# Power_USB.net
KiCad netlist of a schematic drawn in Altium Designer
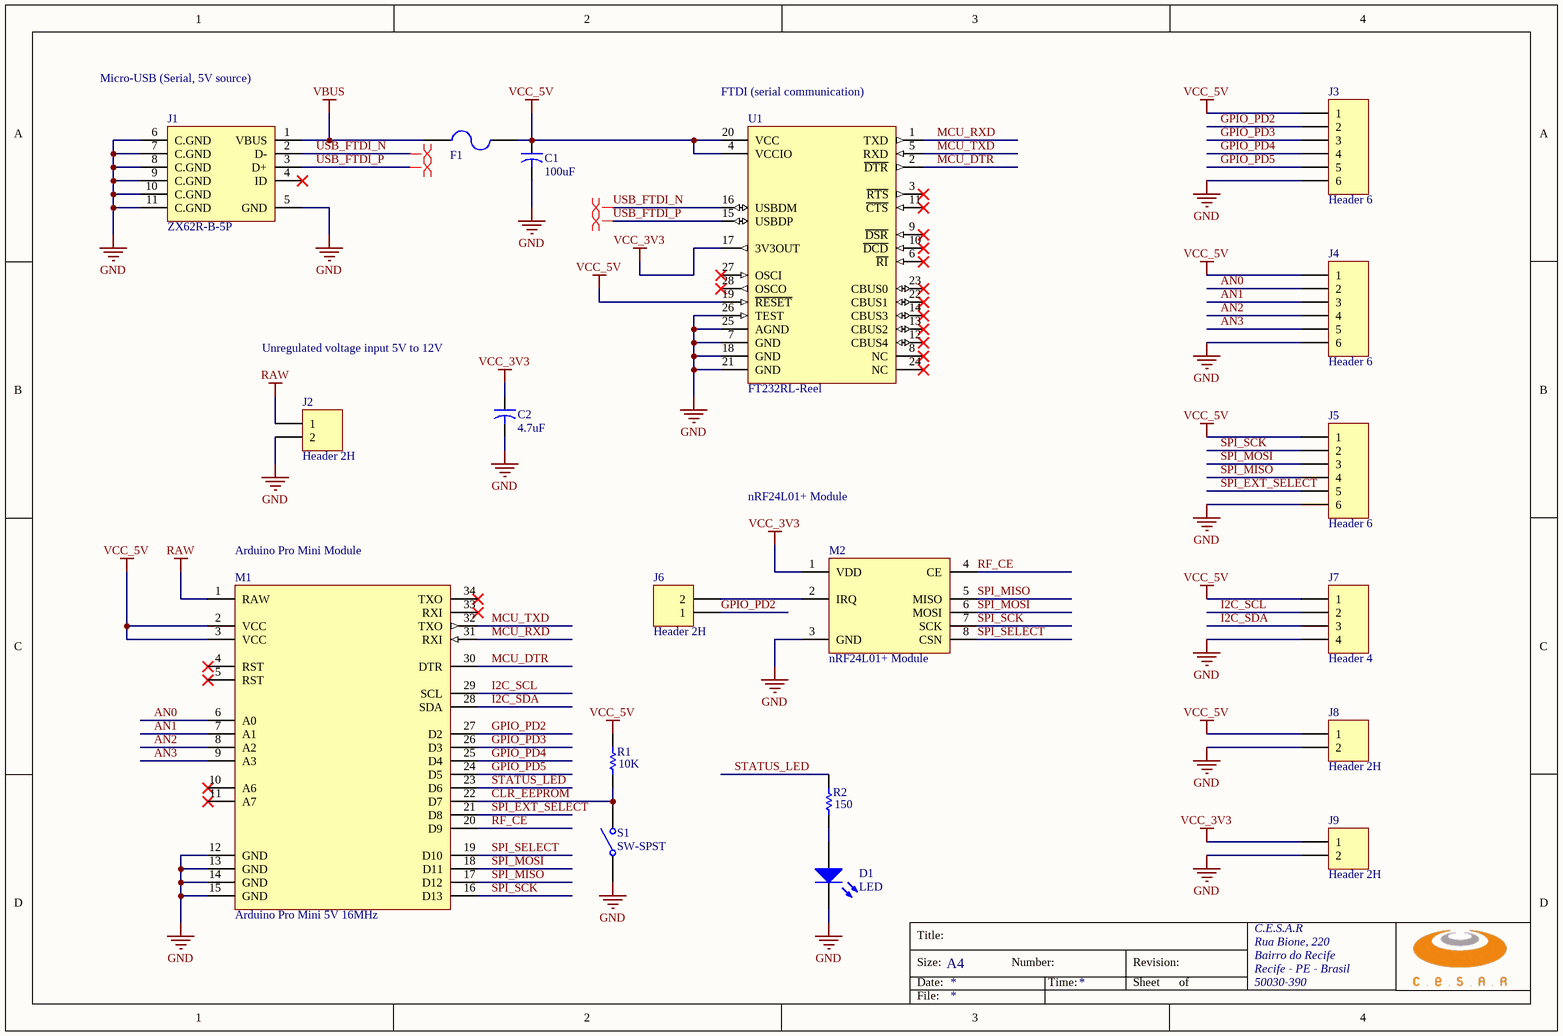
[diagram p0: Power_USB.SchDoc]

(export (version "E")
  (design (tool "Eeschema 10.0.6"))
  (components
    (comp (ref "C1")
      (value "100uF")
      (footprint "CAP Radial 100uF")
      (description "4.7µF 10V Ceramic Capacitor X5R 0603")
      (fields (field (name "Comment") "CAPC1608L") (field (name "PUBLISHER") "Altium Limited"))
      (libsource (lib "KNoT_Thing") (part "CAPC1608L"))
    )
    (comp (ref "C2")
      (value "4.7uF")
      (footprint "CAP RADIAL MINIATURE")
      (description "4.7µF 10V Ceramic Capacitor X5R 0603")
      (fields (field (name "Comment") "CAPC1608L") (field (name "PUBLISHER") "Altium Limited"))
      (libsource (lib "KNoT_Thing") (part "CAPC1608L"))
    )
    (comp (ref "D1")
      (value "LED")
      (footprint "LED")
      (description "Typical RED, GREEN, YELLOW, AMBER GaAs LED")
      (fields (field (name "PUBLISHER") "Altium Limited"))
      (libsource (lib "KNoT_Thing") (part "LED"))
    )
    (comp (ref "F1")
      (value "0402L050SLKR")
      (footprint "0805L")
      (description "PTC Resettable Fuse 6V 500mA Ih Surface Mount 0402 (1005 Metric), Concave")
      (libsource (lib "KNoT_Thing") (part "Fuse 2"))
    )
    (comp (ref "J1")
      (value "ZX62R-B-5P")
      (footprint "Micro USB b")
      (description "USB Connector")
      (libsource (lib "KNoT_Thing") (part "ZX62R-B-5P"))
    )
    (comp (ref "J2")
      (value "Header 2H")
      (footprint "HDR1X2")
      (description "Header, 2-Pin, Right Angle")
      (fields (field (name "PUBLISHER") "Altium Limited"))
      (libsource (lib "KNoT_Thing") (part "Header 2H"))
    )
    (comp (ref "J3")
      (value "Header 6")
      (footprint "HDR1X6")
      (description "Header, 6-Pin")
      (fields (field (name "PUBLISHER") "Altium Limited"))
      (libsource (lib "KNoT_Thing") (part "Header 6"))
    )
    (comp (ref "J4")
      (value "Header 6")
      (footprint "HDR1X6")
      (description "Header, 6-Pin")
      (fields (field (name "PUBLISHER") "Altium Limited"))
      (libsource (lib "KNoT_Thing") (part "Header 6"))
    )
    (comp (ref "J5")
      (value "Header 6")
      (footprint "HDR1X6")
      (description "Header, 6-Pin")
      (fields (field (name "PUBLISHER") "Altium Limited"))
      (libsource (lib "KNoT_Thing") (part "Header 6"))
    )
    (comp (ref "J6")
      (value "Header 2H")
      (footprint "HDR1X2")
      (description "Header, 2-Pin, Right Angle")
      (fields (field (name "PUBLISHER") "Altium Limited"))
      (libsource (lib "") (part "Header 2H_1"))
    )
    (comp (ref "J7")
      (value "Header 4")
      (footprint "HDR1X4")
      (description "Header, 4-Pin")
      (fields (field (name "PUBLISHER") "Altium Limited"))
      (libsource (lib "KNoT_Thing") (part "Header 4"))
    )
    (comp (ref "J8")
      (value "Header 2H")
      (footprint "HDR1X2")
      (description "Header, 2-Pin, Right Angle")
      (fields (field (name "PUBLISHER") "Altium Limited"))
      (libsource (lib "KNoT_Thing") (part "Header 2H"))
    )
    (comp (ref "J9")
      (value "Header 2H")
      (footprint "HDR1X2")
      (description "Header, 2-Pin, Right Angle")
      (fields (field (name "PUBLISHER") "Altium Limited"))
      (libsource (lib "KNoT_Thing") (part "Header 2H"))
    )
    (comp (ref "M1")
      (value "Arduino Pro Mini 5V 16MHz")
      (footprint "Arduino Pro Mini")
      (libsource (lib "KNoT_Thing") (part "Arduino Pro Mini 5V 16MHz"))
    )
    (comp (ref "M2")
      (value "nRF24L01+ Module")
      (footprint "nRF24L01+ Module")
      (libsource (lib "KNoT_Thing") (part "nRF24L01+ Module"))
    )
    (comp (ref "R1")
      (value "10K")
      (footprint "AXIAL-3mm")
      (description "Resistor")
      (fields (field (name "Comment") "Res1") (field (name "PUBLISHER") "Altium Limited"))
      (libsource (lib "KNoT_Thing") (part "Res1"))
    )
    (comp (ref "R2")
      (value "150")
      (footprint "AXIAL-3mm")
      (description "Resistor")
      (fields (field (name "Comment") "Res1") (field (name "PUBLISHER") "Altium Limited"))
      (libsource (lib "KNoT_Thing") (part "Res1"))
    )
    (comp (ref "S1")
      (value "SW-SPST")
      (footprint "SWITCH TS-1181")
      (description "Single-Pole, Single-Throw Switch")
      (fields (field (name "PUBLISHER") "Altium Limited"))
      (libsource (lib "KNoT_Thing") (part "SW-SPST"))
    )
    (comp (ref "U1")
      (value "FT232RL-Reel")
      (footprint "SSOP-28_N")
      (description "USB UART Asynchronous Serial Data Transfer Chip, 28-pin SSOP, Tape and Reel")
      (fields (field (name "MANUFACTURER") "FTDI"))
      (libsource (lib "KNoT_Thing") (part "FT232RL-Reel"))
    )
  )
  (nets
    (net (code "1") (name "/AN0") (class "Default")
      (node (ref "J4") (pin "2") (pinfunction "2_2") (pintype "passive"))
      (node (ref "M1") (pin "6") (pinfunction "A0_6") (pintype "passive"))
    )
    (net (code "2") (name "/AN1") (class "Default")
      (node (ref "J4") (pin "3") (pinfunction "3_3") (pintype "passive"))
      (node (ref "M1") (pin "7") (pinfunction "A1_7") (pintype "passive"))
    )
    (net (code "3") (name "/AN2") (class "Default")
      (node (ref "J4") (pin "4") (pinfunction "4_4") (pintype "passive"))
      (node (ref "M1") (pin "8") (pinfunction "A2_8") (pintype "passive"))
    )
    (net (code "4") (name "/AN3") (class "Default")
      (node (ref "J4") (pin "5") (pinfunction "5_5") (pintype "passive"))
      (node (ref "M1") (pin "9") (pinfunction "A3_9") (pintype "passive"))
    )
    (net (code "5") (name "/CLR_EEPROM") (class "Default")
      (node (ref "M1") (pin "22") (pinfunction "D7_22") (pintype "passive"))
      (node (ref "R1") (pin "2") (pinfunction "2_2") (pintype "passive"))
      (node (ref "S1") (pin "2") (pinfunction "NO_2") (pintype "passive"))
    )
    (net (code "6") (name "/GPIO_PD2") (class "Default")
      (node (ref "J3") (pin "2") (pinfunction "2_2") (pintype "passive"))
      (node (ref "J6") (pin "1") (pinfunction "1_1") (pintype "passive"))
      (node (ref "M1") (pin "27") (pinfunction "D2_27") (pintype "passive"))
    )
    (net (code "7") (name "/GPIO_PD3") (class "Default")
      (node (ref "J3") (pin "3") (pinfunction "3_3") (pintype "passive"))
      (node (ref "M1") (pin "26") (pinfunction "D3_26") (pintype "passive"))
    )
    (net (code "8") (name "/GPIO_PD4") (class "Default")
      (node (ref "J3") (pin "4") (pinfunction "4_4") (pintype "passive"))
      (node (ref "M1") (pin "25") (pinfunction "D4_25") (pintype "passive"))
    )
    (net (code "9") (name "/GPIO_PD5") (class "Default")
      (node (ref "J3") (pin "5") (pinfunction "5_5") (pintype "passive"))
      (node (ref "M1") (pin "24") (pinfunction "D5_24") (pintype "passive"))
    )
    (net (code "10") (name "/I2C_SCL") (class "Default")
      (node (ref "J7") (pin "2") (pinfunction "2_2") (pintype "passive"))
      (node (ref "M1") (pin "29") (pinfunction "SCL_29") (pintype "passive"))
    )
    (net (code "11") (name "/I2C_SDA") (class "Default")
      (node (ref "J7") (pin "3") (pinfunction "3_3") (pintype "passive"))
      (node (ref "M1") (pin "28") (pinfunction "SDA_28") (pintype "passive"))
    )
    (net (code "12") (name "/MCU_DTR") (class "Default")
      (node (ref "M1") (pin "30") (pinfunction "DTR_30") (pintype "passive"))
      (node (ref "U1") (pin "2") (pinfunction "~{DTR}_2") (pintype "output"))
    )
    (net (code "13") (name "/MCU_RXD") (class "Default")
      (node (ref "M1") (pin "31") (pinfunction "RXI_31") (pintype "input"))
      (node (ref "U1") (pin "1") (pinfunction "TXD_1") (pintype "output"))
    )
    (net (code "14") (name "/MCU_TXD") (class "Default")
      (node (ref "M1") (pin "32") (pinfunction "TXO_32") (pintype "output"))
      (node (ref "U1") (pin "5") (pinfunction "RXD_5") (pintype "input"))
    )
    (net (code "15") (name "/RF_CE") (class "Default")
      (node (ref "M1") (pin "20") (pinfunction "D9_20") (pintype "passive"))
      (node (ref "M2") (pin "4") (pinfunction "CE_4") (pintype "passive"))
    )
    (net (code "16") (name "/SPI_EXT_SELECT") (class "Default")
      (node (ref "J5") (pin "5") (pinfunction "5_5") (pintype "passive"))
      (node (ref "M1") (pin "21") (pinfunction "D8_21") (pintype "passive"))
    )
    (net (code "17") (name "/SPI_MISO") (class "Default")
      (node (ref "J5") (pin "4") (pinfunction "4_4") (pintype "passive"))
      (node (ref "M1") (pin "17") (pinfunction "D12_17") (pintype "passive"))
      (node (ref "M2") (pin "5") (pinfunction "MISO_5") (pintype "passive"))
    )
    (net (code "18") (name "/SPI_MOSI") (class "Default")
      (node (ref "J5") (pin "3") (pinfunction "3_3") (pintype "passive"))
      (node (ref "M1") (pin "18") (pinfunction "D11_18") (pintype "passive"))
      (node (ref "M2") (pin "6") (pinfunction "MOSI_6") (pintype "passive"))
    )
    (net (code "19") (name "/SPI_SCK") (class "Default")
      (node (ref "J5") (pin "2") (pinfunction "2_2") (pintype "passive"))
      (node (ref "M1") (pin "16") (pinfunction "D13_16") (pintype "passive"))
      (node (ref "M2") (pin "7") (pinfunction "SCK_7") (pintype "passive"))
    )
    (net (code "20") (name "/SPI_SELECT") (class "Default")
      (node (ref "M1") (pin "19") (pinfunction "D10_19") (pintype "passive"))
      (node (ref "M2") (pin "8") (pinfunction "CSN_8") (pintype "passive"))
    )
    (net (code "21") (name "/STATUS_LED") (class "Default")
      (node (ref "M1") (pin "23") (pinfunction "D6_23") (pintype "passive"))
      (node (ref "R2") (pin "1") (pinfunction "1_1") (pintype "passive"))
    )
    (net (code "22") (name "/USB_FTDI_N") (class "Default")
      (node (ref "J1") (pin "2") (pinfunction "D-_2") (pintype "passive"))
      (node (ref "U1") (pin "16") (pinfunction "USBDM_16") (pintype "bidirectional"))
    )
    (net (code "23") (name "/USB_FTDI_P") (class "Default")
      (node (ref "J1") (pin "3") (pinfunction "D+_3") (pintype "passive"))
      (node (ref "U1") (pin "15") (pinfunction "USBDP_15") (pintype "bidirectional"))
    )
    (net (code "24") (name "GND") (class "Default")
      (node (ref "C1") (pin "2") (pinfunction "2_2") (pintype "passive"))
      (node (ref "C2") (pin "2") (pinfunction "2_2") (pintype "passive"))
      (node (ref "D1") (pin "2") (pinfunction "K_2") (pintype "passive"))
      (node (ref "J1") (pin "10") (pinfunction "C.GND_10") (pintype "passive"))
      (node (ref "J1") (pin "11") (pinfunction "C.GND_11") (pintype "passive"))
      (node (ref "J1") (pin "5") (pinfunction "GND_5") (pintype "passive"))
      (node (ref "J1") (pin "6") (pinfunction "C.GND_6") (pintype "passive"))
      (node (ref "J1") (pin "7") (pinfunction "C.GND_7") (pintype "passive"))
      (node (ref "J1") (pin "8") (pinfunction "C.GND_8") (pintype "passive"))
      (node (ref "J1") (pin "9") (pinfunction "C.GND_9") (pintype "passive"))
      (node (ref "J2") (pin "2") (pinfunction "2_2") (pintype "passive"))
      (node (ref "J3") (pin "6") (pinfunction "6_6") (pintype "passive"))
      (node (ref "J4") (pin "6") (pinfunction "6_6") (pintype "passive"))
      (node (ref "J5") (pin "6") (pinfunction "6_6") (pintype "passive"))
      (node (ref "J7") (pin "4") (pinfunction "4_4") (pintype "passive"))
      (node (ref "J8") (pin "2") (pinfunction "2_2") (pintype "passive"))
      (node (ref "J9") (pin "2") (pinfunction "2_2") (pintype "passive"))
      (node (ref "M1") (pin "12") (pinfunction "GND_12") (pintype "passive"))
      (node (ref "M1") (pin "13") (pinfunction "GND_13") (pintype "passive"))
      (node (ref "M1") (pin "14") (pinfunction "GND_14") (pintype "passive"))
      (node (ref "M1") (pin "15") (pinfunction "GND_15") (pintype "passive"))
      (node (ref "M2") (pin "3") (pinfunction "GND_3") (pintype "passive"))
      (node (ref "S1") (pin "1") (pinfunction "COMMON_1") (pintype "passive"))
      (node (ref "U1") (pin "18") (pinfunction "GND_18") (pintype "power_in"))
      (node (ref "U1") (pin "21") (pinfunction "GND_21") (pintype "power_in"))
      (node (ref "U1") (pin "25") (pinfunction "AGND_25") (pintype "power_in"))
      (node (ref "U1") (pin "26") (pinfunction "TEST_26") (pintype "input"))
      (node (ref "U1") (pin "7") (pinfunction "GND_7") (pintype "power_in"))
    )
    (net (code "25") (name "Net-(D1-A)") (class "Default")
      (node (ref "D1") (pin "1") (pinfunction "A_1") (pintype "passive"))
      (node (ref "R2") (pin "2") (pinfunction "2_2") (pintype "passive"))
    )
    (net (code "26") (name "Net-(M2-IRQ)") (class "Default")
      (node (ref "J6") (pin "2") (pinfunction "2_2") (pintype "passive"))
      (node (ref "M2") (pin "2") (pinfunction "IRQ_2") (pintype "passive"))
    )
    (net (code "27") (name "RAW") (class "Default")
      (node (ref "J2") (pin "1") (pinfunction "1_1") (pintype "passive"))
      (node (ref "M1") (pin "1") (pinfunction "RAW_1") (pintype "passive"))
    )
    (net (code "28") (name "VBUS") (class "Default")
      (node (ref "F1") (pin "1") (pinfunction "1_1") (pintype "passive"))
      (node (ref "J1") (pin "1") (pinfunction "VBUS_1") (pintype "passive"))
    )
    (net (code "29") (name "VCC_3V3") (class "Default")
      (node (ref "C2") (pin "1") (pinfunction "1_1") (pintype "passive"))
      (node (ref "J9") (pin "1") (pinfunction "1_1") (pintype "passive"))
      (node (ref "M2") (pin "1") (pinfunction "VDD_1") (pintype "passive"))
      (node (ref "U1") (pin "17") (pinfunction "3V3OUT_17") (pintype "output"))
    )
    (net (code "30") (name "VCC_5V") (class "Default")
      (node (ref "C1") (pin "1") (pinfunction "1_1") (pintype "passive"))
      (node (ref "F1") (pin "2") (pinfunction "2_2") (pintype "passive"))
      (node (ref "J3") (pin "1") (pinfunction "1_1") (pintype "passive"))
      (node (ref "J4") (pin "1") (pinfunction "1_1") (pintype "passive"))
      (node (ref "J5") (pin "1") (pinfunction "1_1") (pintype "passive"))
      (node (ref "J7") (pin "1") (pinfunction "1_1") (pintype "passive"))
      (node (ref "J8") (pin "1") (pinfunction "1_1") (pintype "passive"))
      (node (ref "M1") (pin "2") (pinfunction "VCC_2") (pintype "passive"))
      (node (ref "M1") (pin "3") (pinfunction "VCC_3") (pintype "passive"))
      (node (ref "R1") (pin "1") (pinfunction "1_1") (pintype "passive"))
      (node (ref "U1") (pin "19") (pinfunction "~{RESET}_19") (pintype "input"))
      (node (ref "U1") (pin "20") (pinfunction "VCC_20") (pintype "power_in"))
      (node (ref "U1") (pin "4") (pinfunction "VCCIO_4") (pintype "power_in"))
    )
    (net (code "31") (name "unconnected-(J1-ID-Pad4)") (class "Default")
      (node (ref "J1") (pin "4") (pinfunction "ID_4") (pintype "passive+no_connect"))
    )
    (net (code "32") (name "unconnected-(M1-A6-Pad10)") (class "Default")
      (node (ref "M1") (pin "10") (pinfunction "A6_10") (pintype "passive+no_connect"))
    )
    (net (code "33") (name "unconnected-(M1-A7-Pad11)") (class "Default")
      (node (ref "M1") (pin "11") (pinfunction "A7_11") (pintype "passive+no_connect"))
    )
    (net (code "34") (name "unconnected-(M1-RST-Pad4)") (class "Default")
      (node (ref "M1") (pin "4") (pinfunction "RST_4") (pintype "passive+no_connect"))
    )
    (net (code "35") (name "unconnected-(M1-RST-Pad5)") (class "Default")
      (node (ref "M1") (pin "5") (pinfunction "RST_5") (pintype "passive+no_connect"))
    )
    (net (code "36") (name "unconnected-(M1-RXI-Pad33)") (class "Default")
      (node (ref "M1") (pin "33") (pinfunction "RXI_33") (pintype "passive+no_connect"))
    )
    (net (code "37") (name "unconnected-(M1-TXO-Pad34)") (class "Default")
      (node (ref "M1") (pin "34") (pinfunction "TXO_34") (pintype "passive+no_connect"))
    )
    (net (code "38") (name "unconnected-(U1-CBUS0-Pad23)") (class "Default")
      (node (ref "U1") (pin "23") (pinfunction "CBUS0_23") (pintype "bidirectional+no_connect"))
    )
    (net (code "39") (name "unconnected-(U1-CBUS1-Pad22)") (class "Default")
      (node (ref "U1") (pin "22") (pinfunction "CBUS1_22") (pintype "bidirectional+no_connect"))
    )
    (net (code "40") (name "unconnected-(U1-CBUS2-Pad13)") (class "Default")
      (node (ref "U1") (pin "13") (pinfunction "CBUS2_13") (pintype "bidirectional+no_connect"))
    )
    (net (code "41") (name "unconnected-(U1-CBUS3-Pad14)") (class "Default")
      (node (ref "U1") (pin "14") (pinfunction "CBUS3_14") (pintype "bidirectional+no_connect"))
    )
    (net (code "42") (name "unconnected-(U1-CBUS4-Pad12)") (class "Default")
      (node (ref "U1") (pin "12") (pinfunction "CBUS4_12") (pintype "bidirectional+no_connect"))
    )
    (net (code "43") (name "unconnected-(U1-NC-Pad8)") (class "Default")
      (node (ref "U1") (pin "8") (pinfunction "NC_8") (pintype "passive+no_connect"))
    )
    (net (code "44") (name "unconnected-(U1-NC-Pad24)") (class "Default")
      (node (ref "U1") (pin "24") (pinfunction "NC_24") (pintype "passive+no_connect"))
    )
    (net (code "45") (name "unconnected-(U1-OSCI-Pad27)") (class "Default")
      (node (ref "U1") (pin "27") (pinfunction "OSCI_27") (pintype "input+no_connect"))
    )
    (net (code "46") (name "unconnected-(U1-OSCO-Pad28)") (class "Default")
      (node (ref "U1") (pin "28") (pinfunction "OSCO_28") (pintype "output+no_connect"))
    )
    (net (code "47") (name "unconnected-(U1-~{CTS}-Pad11)") (class "Default")
      (node (ref "U1") (pin "11") (pinfunction "~{CTS}_11") (pintype "input+no_connect"))
    )
    (net (code "48") (name "unconnected-(U1-~{DCD}-Pad10)") (class "Default")
      (node (ref "U1") (pin "10") (pinfunction "~{DCD}_10") (pintype "input+no_connect"))
    )
    (net (code "49") (name "unconnected-(U1-~{DSR}-Pad9)") (class "Default")
      (node (ref "U1") (pin "9") (pinfunction "~{DSR}_9") (pintype "input+no_connect"))
    )
    (net (code "50") (name "unconnected-(U1-~{RI}-Pad6)") (class "Default")
      (node (ref "U1") (pin "6") (pinfunction "~{RI}_6") (pintype "input+no_connect"))
    )
    (net (code "51") (name "unconnected-(U1-~{RTS}-Pad3)") (class "Default")
      (node (ref "U1") (pin "3") (pinfunction "~{RTS}_3") (pintype "output+no_connect"))
    )
  )
)
